# Power.net
KiCad netlist of a schematic drawn in Altium Designer
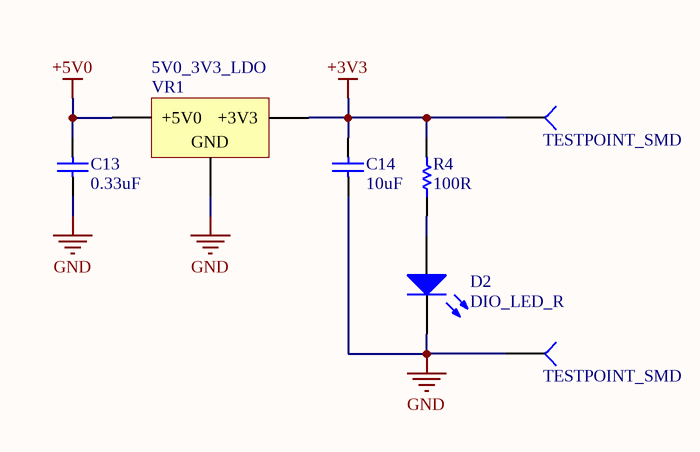
[diagram p0: Power.SchDoc]

(export (version "E")
  (design (tool "Eeschema 10.0.6"))
  (components
    (comp (ref "C13")
      (value "0.33uF")
      (footprint "CAPC0603(1608)55_N")
      (description "CAP CER 0.33UF 16V X7R 0603")
      (fields
        (field (name "PART NUMBER") "GRM188R71C334KA01D")
        (field (name "MANUFACTURER") "Murata Electronics North America")
      )
      (libsource (lib "UWRT_Schematic_Library_2019") (part "CAP_0.33uF_16V_0603"))
    )
    (comp (ref "C14")
      (value "10uF")
      (footprint "CAPC0603(1608)55_N")
      (description "CAP CER 10UF 10V X5R 0603")
      (fields (field (name "PART NUMBER") "CC0603MRX5R6BB106") (field (name "MANUFACTURER") "Yageo"))
      (libsource (lib "UWRT_Schematic_Library_2019") (part "CAP_10uF_0603"))
    )
    (comp (ref "D2")
      (value "DIO_LED_R")
      (footprint "LED_0805")
      (description "LED RED DIFFUSED 0805 SMD")
      (fields (field (name "PART NUMBER") "LS R976-NR-1") (field (name "MANUFACTURER") "OSRAM"))
      (libsource (lib "UWRT_Schematic_Library_2019") (part "DIO_LED_R"))
    )
    (comp (ref "R4")
      (value "100R")
      (footprint "RESC0603(1608)_N")
      (description "RES SMD 100 OHM 1% 1/10W 0603")
      (fields (field (name "MANUFACTURER") "Yageo") (field (name "TOLERANCE") "1%"))
      (libsource (lib "UWRT_Schematic_Library_2019") (part "RES_100R_0603"))
    )
    (comp (ref "TP3")
      (value "TESTPOINT_SMD")
      (footprint "TESTPOINT")
      (libsource (lib "UWRT_Schematic_Library_2019") (part "TESTPOINT_SMD"))
    )
    (comp (ref "TP4")
      (value "TESTPOINT_SMD")
      (footprint "TESTPOINT")
      (libsource (lib "UWRT_Schematic_Library_2019") (part "TESTPOINT_SMD"))
    )
    (comp (ref "VR1")
      (value "5V0_3V3_LDO")
      (footprint "VOLTAGE_REGULATOR")
      (description "IC REG LINEAR 3.3V 1A DPAK")
      (fields (field (name "PART NUMBER") "NCP1117DT33T5G") (field (name "MANUFACTURER") "ON Semiconductor"))
      (libsource (lib "UWRT_Schematic_Library_2019") (part "5V0_3V3_LDO"))
    )
  )
  (nets
    (net (code "1") (name "+3V3") (class "Default")
      (node (ref "C14") (pin "2") (pinfunction "2_2") (pintype "passive"))
      (node (ref "R4") (pin "2") (pinfunction "2_2") (pintype "passive"))
      (node (ref "TP3") (pin "1") (pinfunction "=value_1") (pintype "passive"))
      (node (ref "VR1") (pin "3") (pinfunction "+3V3_3") (pintype "passive"))
    )
    (net (code "2") (name "+5V0") (class "Default")
      (node (ref "C13") (pin "2") (pinfunction "2_2") (pintype "passive"))
      (node (ref "VR1") (pin "1") (pinfunction "+5V0_1") (pintype "passive"))
    )
    (net (code "3") (name "GND") (class "Default")
      (node (ref "C13") (pin "1") (pinfunction "1_1") (pintype "passive"))
      (node (ref "C14") (pin "1") (pinfunction "1_1") (pintype "passive"))
      (node (ref "D2") (pin "2") (pinfunction "K_2") (pintype "passive"))
      (node (ref "TP4") (pin "1") (pinfunction "=value_1") (pintype "passive"))
      (node (ref "VR1") (pin "2") (pinfunction "GND_2") (pintype "passive"))
    )
    (net (code "4") (name "Net-(D2-A)") (class "Default")
      (node (ref "D2") (pin "1") (pinfunction "A_1") (pintype "passive"))
      (node (ref "R4") (pin "1") (pinfunction "1_1") (pintype "passive"))
    )
  )
)
